# AuxHalfH.net
KiCad netlist of a schematic drawn in Altium Designer
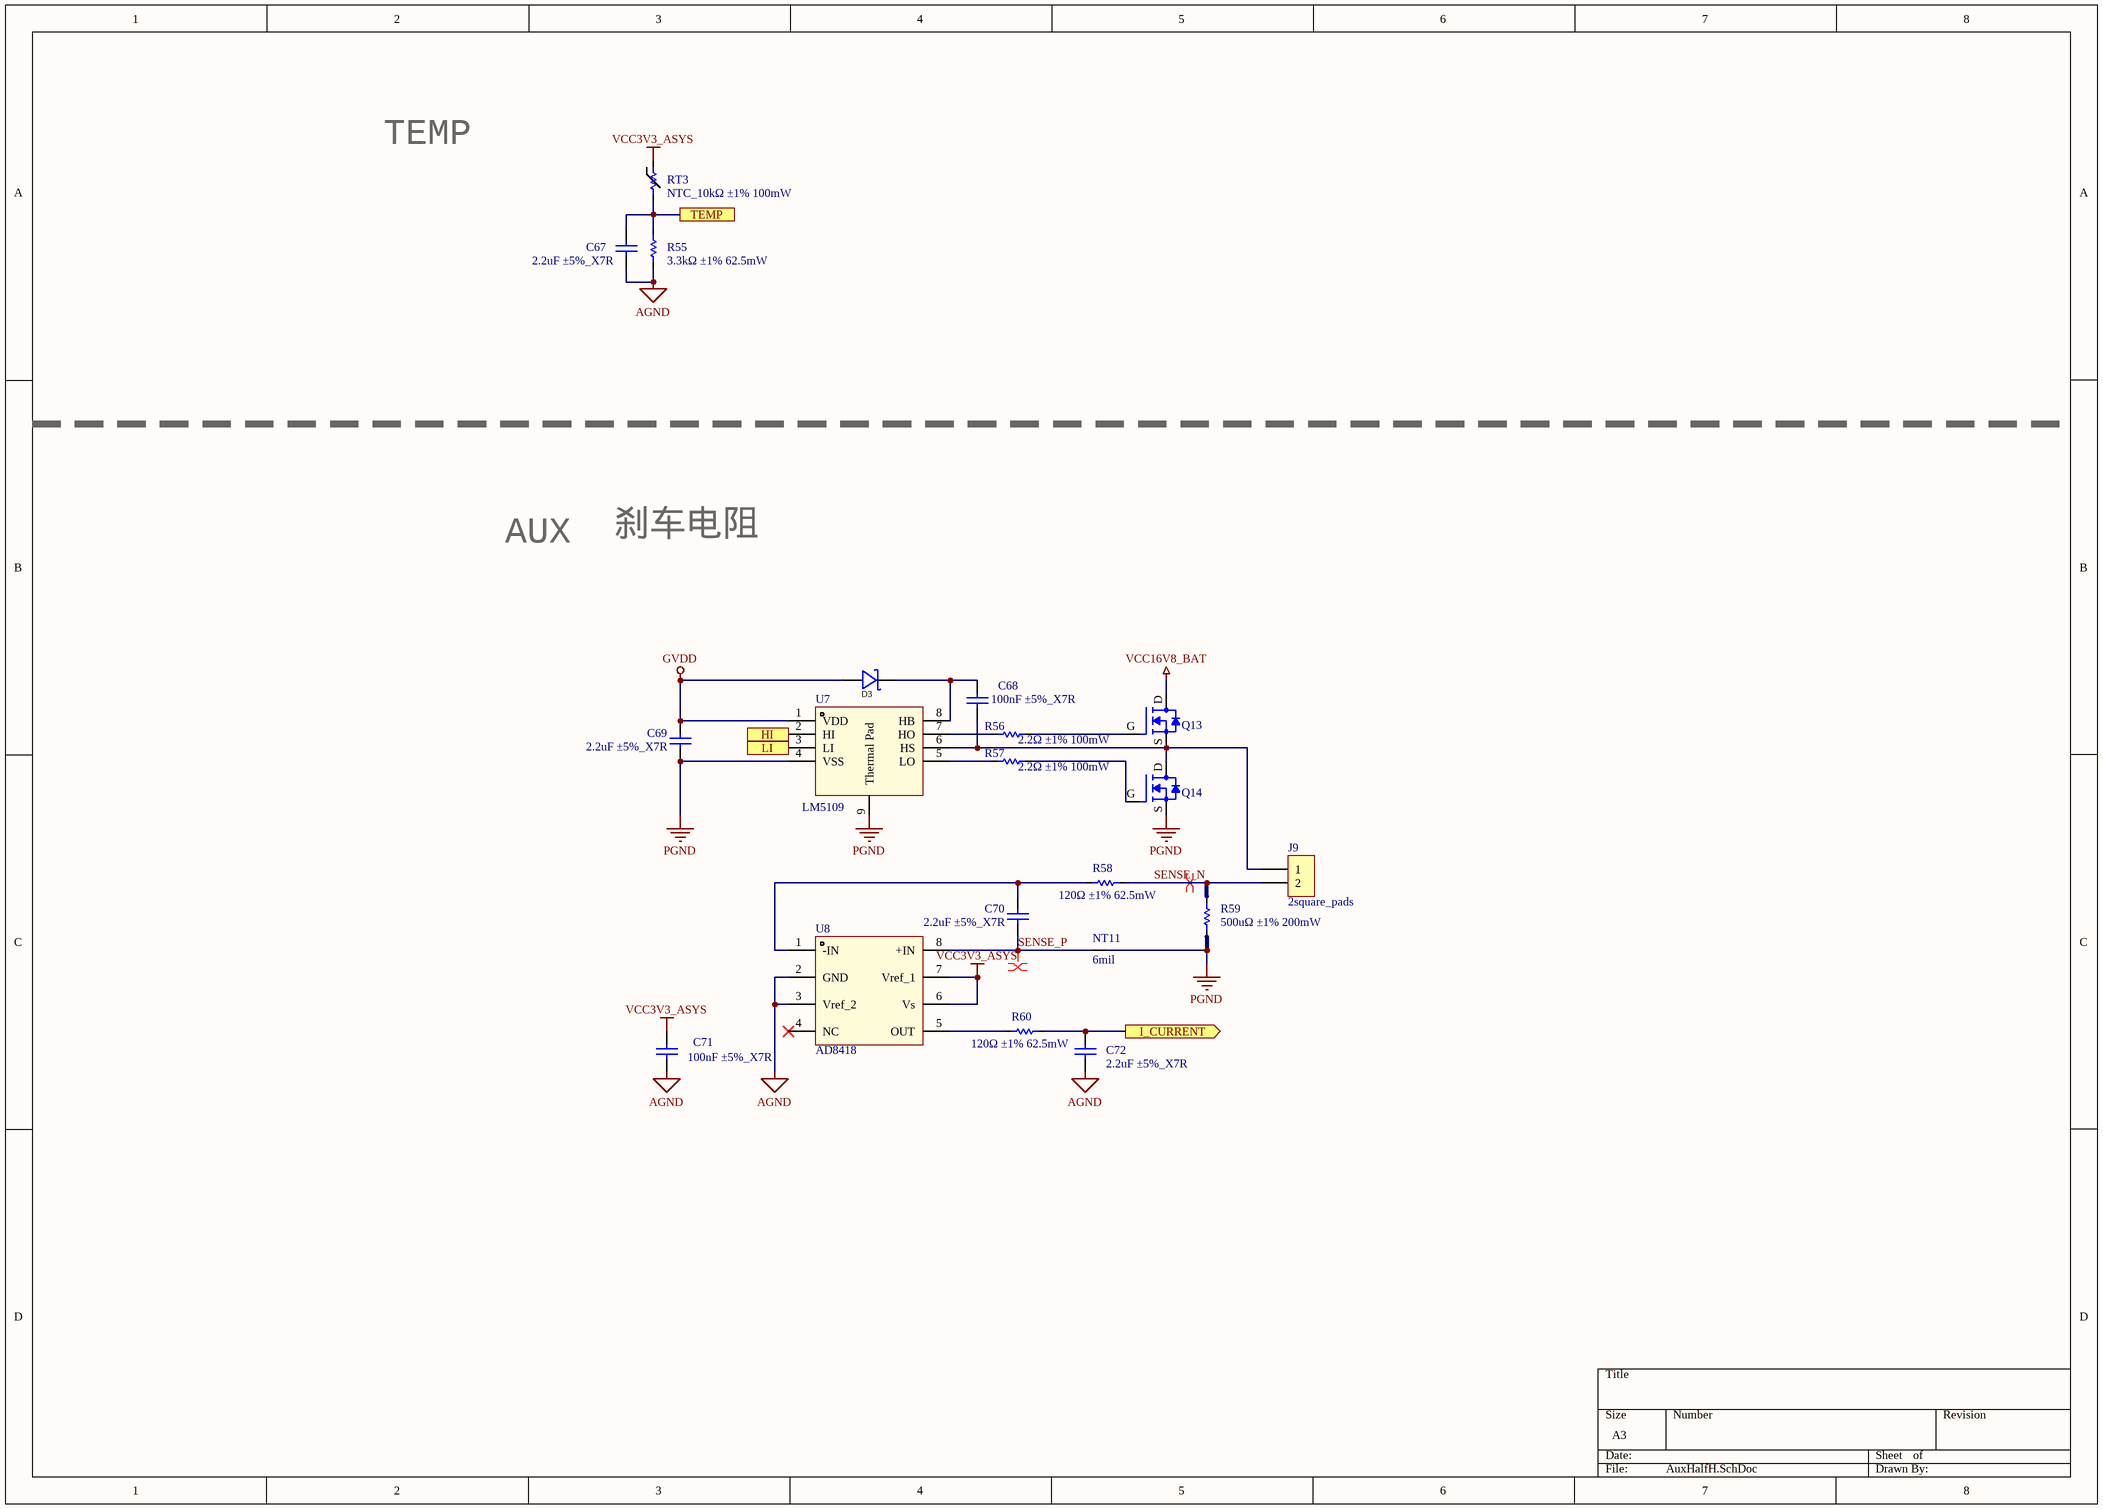
[diagram p0: AuxHalfH.SchDoc]

(export (version "E")
  (design (tool "Eeschema 10.0.6"))
  (components
    (comp (ref "C67")
      (value "2.2uF ±5%_X7R")
      (footprint "C0402")
      (description "Capacitor")
      (fields (field (name "PUBLISHER") "Altium Limited"))
      (libsource (lib "Component") (part "Cap"))
    )
    (comp (ref "C68")
      (value "100nF ±5%_X7R")
      (footprint "C0603")
      (description "Capacitor")
      (fields (field (name "PUBLISHER") "Altium Limited"))
      (libsource (lib "Component") (part "Cap"))
    )
    (comp (ref "C69")
      (value "2.2uF ±5%_X7R")
      (footprint "C0603")
      (description "Capacitor")
      (fields (field (name "PUBLISHER") "Altium Limited"))
      (libsource (lib "Component") (part "Cap"))
    )
    (comp (ref "C70")
      (value "2.2uF ±5%_X7R")
      (footprint "C0402")
      (description "Capacitor")
      (fields (field (name "PUBLISHER") "Altium Limited"))
      (libsource (lib "Component") (part "Cap"))
    )
    (comp (ref "C71")
      (value "100nF ±5%_X7R")
      (footprint "C0402")
      (description "Capacitor")
      (fields (field (name "PUBLISHER") "Altium Limited"))
      (libsource (lib "Component") (part "Cap"))
    )
    (comp (ref "C72")
      (value "2.2uF ±5%_X7R")
      (footprint "C0402")
      (description "Capacitor")
      (fields (field (name "PUBLISHER") "Altium Limited"))
      (libsource (lib "Component") (part "Cap"))
    )
    (comp (ref "D3")
      (value "B340A-13-F")
      (footprint "SMA_L4.4-W2.6-LS5.0-RD")
      (description "直流反向耐压(Vr):40V;平均整流电流(Io):3A;正向压降(Vf):500mV@3A;")
      (fields (field (name "MANUFACTURER") "DIODES(美台)"))
      (libsource (lib "Component") (part "Diode_Schottky"))
    )
    (comp (ref "J9")
      (value "2square_pads")
      (footprint "2pads_square")
      (libsource (lib "Connectivity_Plugs") (part "2square_pads"))
    )
    (comp (ref "NT11") (value "6mil") (footprint "NETTIE_6mil") (libsource (lib "Component") (part "NETTIE")))
    (comp (ref "Q13")
      (value "BSC027N04LSG")
      (footprint "NRVTS10100EMFST1G")
      (description "MOSFET – Power, Single,\r\nN-Channel, PG-TDSON-8\r\nSuperSO8 5x6\r\n40 V, 139 A")
      (fields
        (field (name "MANUFACTURER") "ON Semiconductor")
        (field (name "MANUFACTURER PART NUMBER") "NTMFS4935NT1G")
      )
      (libsource (lib "Component") (part "MOSFET-N"))
    )
    (comp (ref "Q14")
      (value "BSC027N04LSG")
      (footprint "NRVTS10100EMFST1G")
      (description "MOSFET – Power, Single,\r\nN-Channel, PG-TDSON-8\r\nSuperSO8 5x6\r\n40 V, 139 A")
      (fields
        (field (name "MANUFACTURER") "ON Semiconductor")
        (field (name "MANUFACTURER PART NUMBER") "NTMFS4935NT1G")
      )
      (libsource (lib "Component") (part "MOSFET-N"))
    )
    (comp (ref "R55")
      (value "3.3kΩ ±1% 62.5mW")
      (footprint "R0402")
      (description "Resistor")
      (fields (field (name "PUBLISHER") "Altium Limited"))
      (libsource (lib "Component") (part "Res"))
    )
    (comp (ref "R56")
      (value "2.2Ω ±1% 100mW")
      (footprint "R0402")
      (description "Resistor")
      (fields (field (name "PUBLISHER") "Altium Limited"))
      (libsource (lib "Component") (part "Res"))
    )
    (comp (ref "R57")
      (value "2.2Ω ±1% 100mW")
      (footprint "R0402")
      (description "Resistor")
      (fields (field (name "PUBLISHER") "Altium Limited"))
      (libsource (lib "Component") (part "Res"))
    )
    (comp (ref "R58")
      (value "120Ω ±1% 62.5mW")
      (footprint "R0402")
      (description "Resistor")
      (fields (field (name "PUBLISHER") "Altium Limited"))
      (libsource (lib "Component") (part "Res"))
    )
    (comp (ref "R59")
      (value "500uΩ ±1% 200mW")
      (footprint "R2512")
      (description "Resistor")
      (fields (field (name "PUBLISHER") "Altium Limited"))
      (libsource (lib "Component") (part "Res"))
    )
    (comp (ref "R60")
      (value "120Ω ±1% 62.5mW")
      (footprint "R0402")
      (description "Resistor")
      (fields (field (name "PUBLISHER") "Altium Limited"))
      (libsource (lib "Component") (part "Res"))
    )
    (comp (ref "RT3")
      (value "NTC_10kΩ ±1% 100mW")
      (footprint "R0402")
      (description "THERMISTOR 10K OHM NTC 0402 SMD")
      (libsource (lib "Component") (part "TEMP RES"))
    )
    (comp (ref "U7")
      (value "LM5109")
      (footprint "SON80P400X80_HS-9N")
      (description "DRIVER, MOSFET, HALF BRIDGE, WSON-8, 1A")
      (libsource (lib "IC") (part "LM5109"))
    )
    (comp (ref "U8")
      (value "AD8418")
      (footprint "MSOP-8_L3.0-W3.0-P0.65-LS5.0-BL")
      (description "ANALOG DEVICES Current Sense Amplifier, Bidirectional, 1, 130 µA, NSOIC")
      (libsource (lib "IC") (part "AD8418WBRZ"))
    )
  )
  (nets
    (net (code "1") (name "/HI") (class "Default")
      (node (ref "U7") (pin "2") (pinfunction "HI_2") (pintype "passive"))
    )
    (net (code "2") (name "/I_CURRENT") (class "Default")
      (node (ref "C72") (pin "2") (pinfunction "2_2") (pintype "passive"))
      (node (ref "R60") (pin "1") (pinfunction "1_1") (pintype "passive"))
    )
    (net (code "3") (name "/LI") (class "Default")
      (node (ref "U7") (pin "3") (pinfunction "LI_3") (pintype "passive"))
    )
    (net (code "4") (name "/SENSE_N") (class "Default")
      (node (ref "J9") (pin "2") (pinfunction "2_2") (pintype "passive"))
      (node (ref "R58") (pin "1") (pinfunction "1_1") (pintype "passive"))
      (node (ref "R59") (pin "1") (pinfunction "1_1") (pintype "passive"))
    )
    (net (code "5") (name "/SENSE_P") (class "Default")
      (node (ref "C70") (pin "1") (pinfunction "1_1") (pintype "passive"))
      (node (ref "NT11") (pin "2") (pinfunction "2_2") (pintype "passive"))
      (node (ref "U8") (pin "8") (pinfunction "+IN_8") (pintype "passive"))
    )
    (net (code "6") (name "/TEMP") (class "Default")
      (node (ref "C67") (pin "2") (pinfunction "2_2") (pintype "passive"))
      (node (ref "R55") (pin "2") (pinfunction "2_2") (pintype "passive"))
      (node (ref "RT3") (pin "2") (pinfunction "2_2") (pintype "passive"))
    )
    (net (code "7") (name "AGND") (class "Default")
      (node (ref "C67") (pin "1") (pinfunction "1_1") (pintype "passive"))
      (node (ref "C71") (pin "1") (pinfunction "1_1") (pintype "passive"))
      (node (ref "C72") (pin "1") (pinfunction "1_1") (pintype "passive"))
      (node (ref "R55") (pin "1") (pinfunction "1_1") (pintype "passive"))
      (node (ref "U8") (pin "2") (pinfunction "GND_2") (pintype "passive"))
      (node (ref "U8") (pin "3") (pinfunction "Vref_2_3") (pintype "passive"))
    )
    (net (code "8") (name "GVDD") (class "Default")
      (node (ref "C69") (pin "2") (pinfunction "2_2") (pintype "passive"))
      (node (ref "D3") (pin "2") (pinfunction "A_2") (pintype "passive"))
      (node (ref "U7") (pin "1") (pinfunction "VDD_1") (pintype "passive"))
    )
    (net (code "9") (name "Net-(D3-K)") (class "Default")
      (node (ref "C68") (pin "2") (pinfunction "2_2") (pintype "passive"))
      (node (ref "D3") (pin "1") (pinfunction "K_1") (pintype "passive"))
      (node (ref "U7") (pin "8") (pinfunction "HB_8") (pintype "passive"))
    )
    (net (code "10") (name "Net-(Q13-PadG)") (class "Default")
      (node (ref "Q13") (pin "G") (pinfunction "G_G") (pintype "passive"))
      (node (ref "R56") (pin "1") (pinfunction "1_1") (pintype "passive"))
    )
    (net (code "11") (name "Net-(Q14-PadG)") (class "Default")
      (node (ref "Q14") (pin "G") (pinfunction "G_G") (pintype "passive"))
      (node (ref "R57") (pin "1") (pinfunction "1_1") (pintype "passive"))
    )
    (net (code "12") (name "Net-(U7-HO)") (class "Default")
      (node (ref "R56") (pin "2") (pinfunction "2_2") (pintype "passive"))
      (node (ref "U7") (pin "7") (pinfunction "HO_7") (pintype "passive"))
    )
    (net (code "13") (name "Net-(U7-HS)") (class "Default")
      (node (ref "C68") (pin "1") (pinfunction "1_1") (pintype "passive"))
      (node (ref "J9") (pin "1") (pinfunction "1_1") (pintype "passive"))
      (node (ref "Q13") (pin "S") (pinfunction "S_S") (pintype "passive"))
      (node (ref "Q14") (pin "D") (pinfunction "D_D") (pintype "passive"))
      (node (ref "U7") (pin "6") (pinfunction "HS_6") (pintype "passive"))
    )
    (net (code "14") (name "Net-(U7-LO)") (class "Default")
      (node (ref "R57") (pin "2") (pinfunction "2_2") (pintype "passive"))
      (node (ref "U7") (pin "5") (pinfunction "LO_5") (pintype "passive"))
    )
    (net (code "15") (name "Net-(U8--IN)") (class "Default")
      (node (ref "C70") (pin "2") (pinfunction "2_2") (pintype "passive"))
      (node (ref "R58") (pin "2") (pinfunction "2_2") (pintype "passive"))
      (node (ref "U8") (pin "1") (pinfunction "-IN_1") (pintype "passive"))
    )
    (net (code "16") (name "Net-(U8-OUT)") (class "Default")
      (node (ref "R60") (pin "2") (pinfunction "2_2") (pintype "passive"))
      (node (ref "U8") (pin "5") (pinfunction "OUT_5") (pintype "passive"))
    )
    (net (code "17") (name "PGND") (class "Default")
      (node (ref "C69") (pin "1") (pinfunction "1_1") (pintype "passive"))
      (node (ref "NT11") (pin "1") (pinfunction "1_1") (pintype "passive"))
      (node (ref "Q14") (pin "S") (pinfunction "S_S") (pintype "passive"))
      (node (ref "R59") (pin "2") (pinfunction "2_2") (pintype "passive"))
      (node (ref "U7") (pin "4") (pinfunction "VSS_4") (pintype "passive"))
      (node (ref "U7") (pin "9") (pinfunction "Thermal_Pad_9") (pintype "passive"))
    )
    (net (code "18") (name "VCC3V3_ASYS") (class "Default")
      (node (ref "C71") (pin "2") (pinfunction "2_2") (pintype "passive"))
      (node (ref "RT3") (pin "1") (pinfunction "1_1") (pintype "passive"))
      (node (ref "U8") (pin "6") (pinfunction "Vs_6") (pintype "passive"))
      (node (ref "U8") (pin "7") (pinfunction "Vref_1_7") (pintype "passive"))
    )
    (net (code "19") (name "VCC16V8_BAT") (class "Default")
      (node (ref "Q13") (pin "D") (pinfunction "D_D") (pintype "passive"))
    )
    (net (code "20") (name "unconnected-(U8-NC-Pad4)") (class "Default")
      (node (ref "U8") (pin "4") (pinfunction "NC_4") (pintype "passive+no_connect"))
    )
  )
)
